# MyCar.net
KiCad netlist of a schematic drawn in Altium Designer
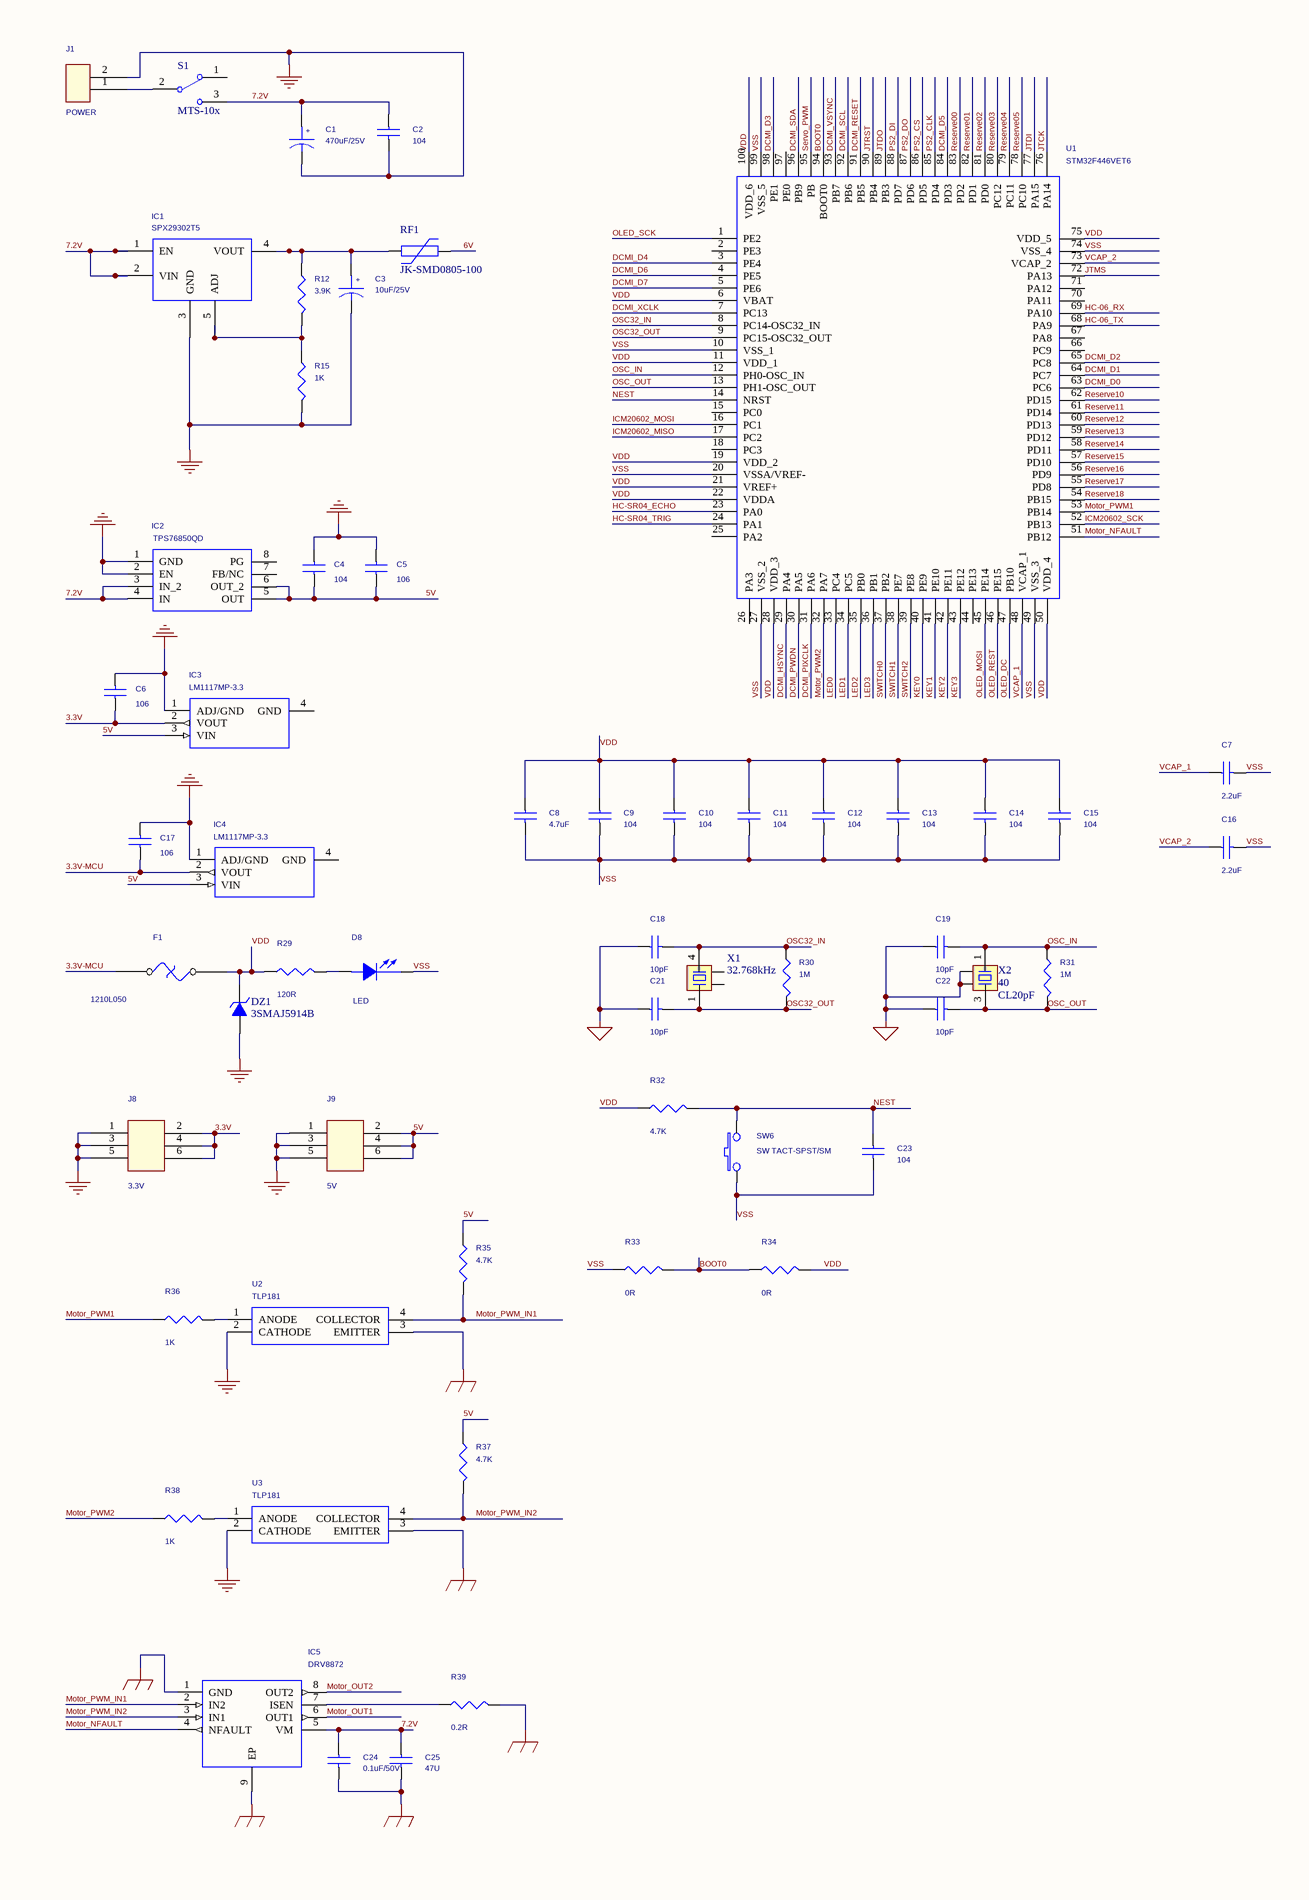
[diagram p0: MyCar.SchDoc, left]
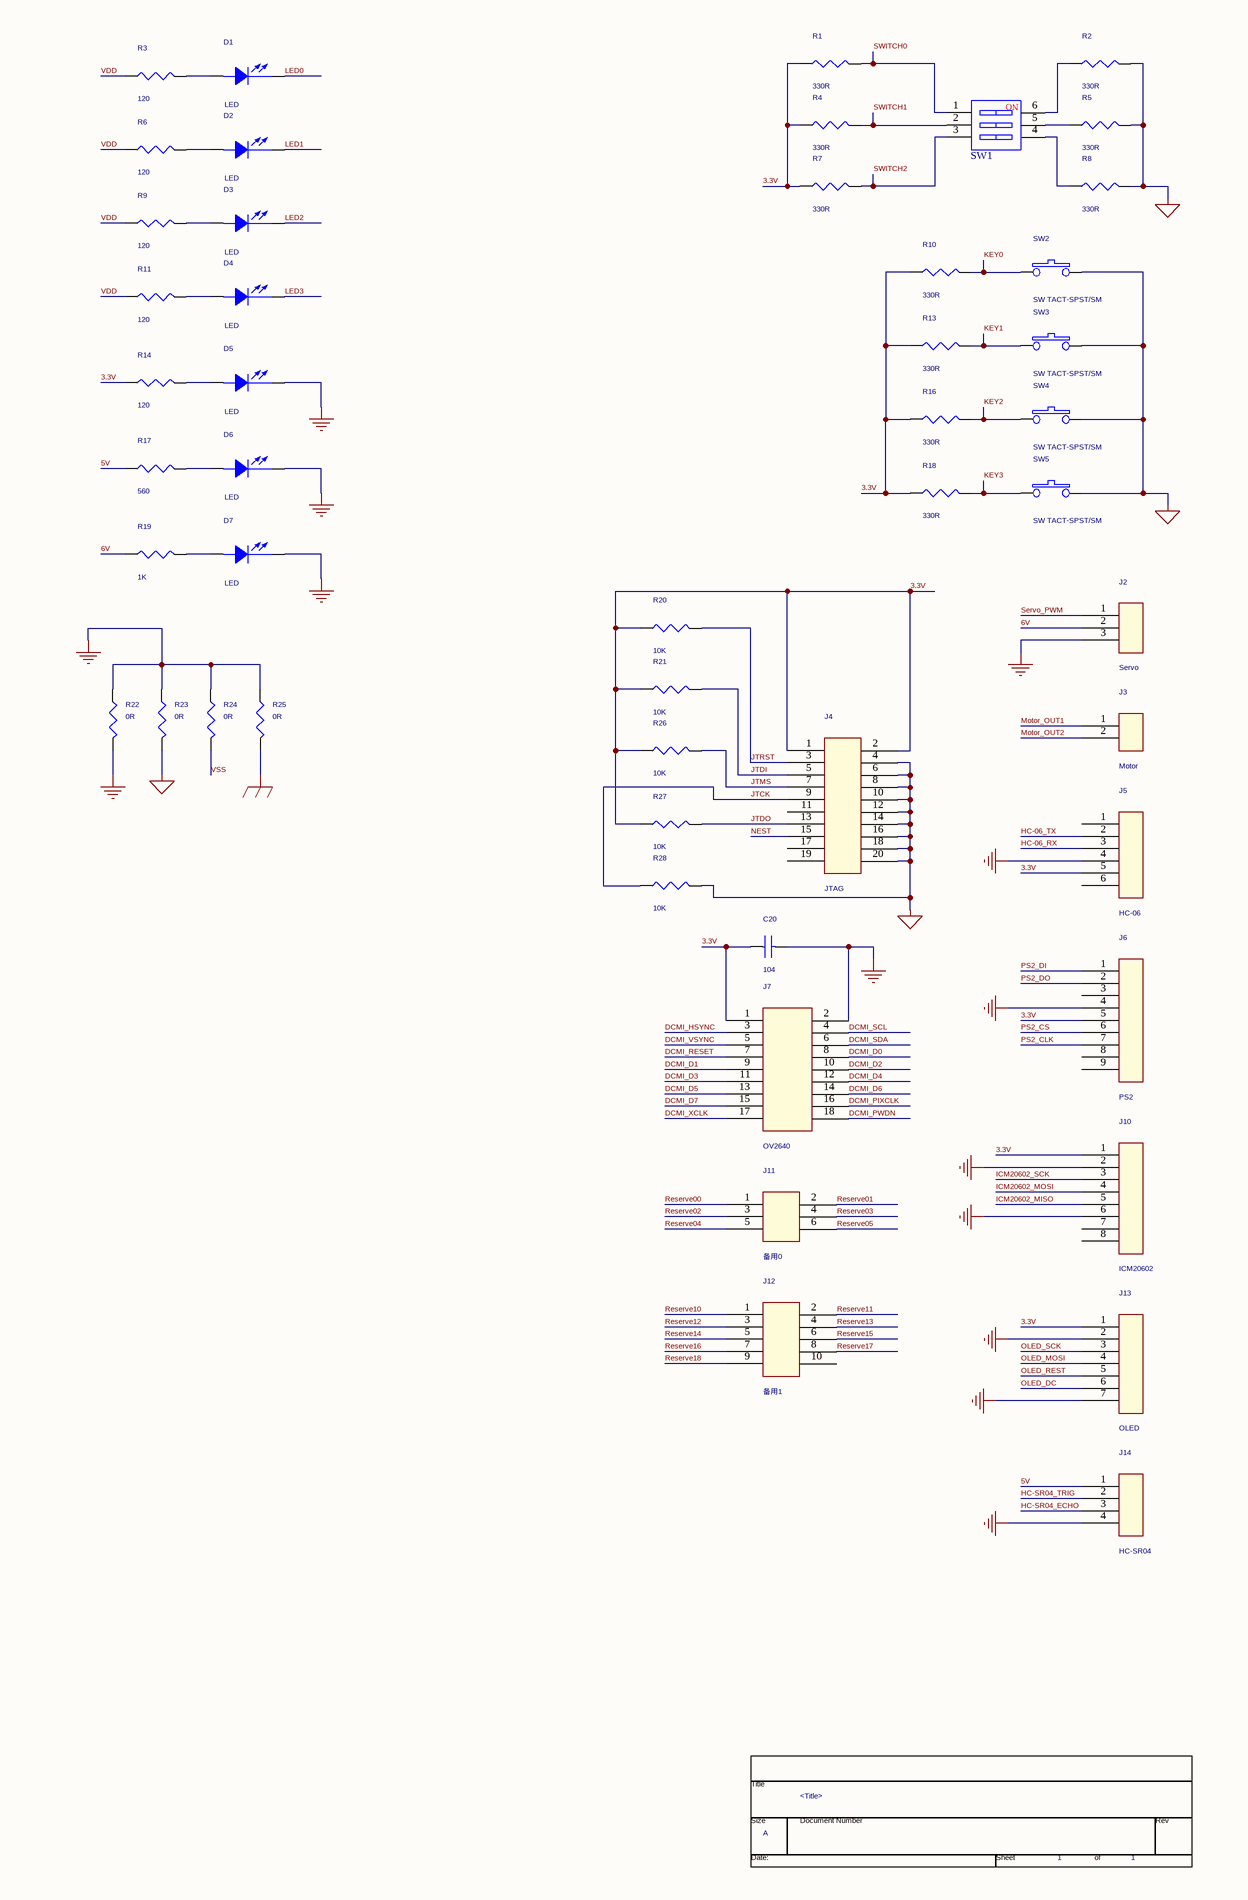
[diagram p1: MyCar.SchDoc, right]

(export (version "E")
  (design (tool "Eeschema 10.0.6"))
  (components
    (comp (ref "*")
      (value "TitleBlock0")
      (fields
        (field (name "TITLE") "<Title>")
        (field (name "PAGE SIZE") "A")
        (field (name "PAGE NUMBER") "1")
        (field (name "PAGE COUNT") "1")
      )
      (libsource (lib "*") (part "TitleBlock0"))
    )
    (comp (ref "C1") (value "470uF/25V") (footprint "CAP 3.5*8*11.5") (libsource (lib "*") (part "CAP POL")))
    (comp (ref "C2") (value "104") (footprint "C 0805_M") (libsource (lib "*") (part "CAP NP")))
    (comp (ref "C3") (value "10uF/25V") (footprint "CAP 2.0*5*7") (libsource (lib "*") (part "CAP POL")))
    (comp (ref "C4") (value "104") (footprint "C 0805_M") (libsource (lib "*") (part "CAP NP")))
    (comp (ref "C5") (value "106") (footprint "C 0805_M") (libsource (lib "*") (part "CAP NP")))
    (comp (ref "C6") (value "106") (footprint "C 0805_M") (libsource (lib "*") (part "CAP NP")))
    (comp (ref "C7") (value "2.2uF") (footprint "CD A(3216)") (libsource (lib "*") (part "CAP NP")))
    (comp (ref "C8") (value "4.7uF") (footprint "C 1210_M") (libsource (lib "*") (part "CAP NP")))
    (comp (ref "C9") (value "104") (footprint "C 0805_M") (libsource (lib "*") (part "CAP NP")))
    (comp (ref "C10") (value "104") (footprint "C 0805_M") (libsource (lib "*") (part "CAP NP")))
    (comp (ref "C11") (value "104") (footprint "C 0805_M") (libsource (lib "*") (part "CAP NP")))
    (comp (ref "C12") (value "104") (footprint "C 0805_M") (libsource (lib "*") (part "CAP NP")))
    (comp (ref "C13") (value "104") (footprint "C 0805_M") (libsource (lib "*") (part "CAP NP")))
    (comp (ref "C14") (value "104") (footprint "C 0805_M") (libsource (lib "*") (part "CAP NP")))
    (comp (ref "C15") (value "104") (footprint "C 0805_M") (libsource (lib "*") (part "CAP NP")))
    (comp (ref "C16") (value "2.2uF") (footprint "CD A(3216)") (libsource (lib "*") (part "CAP NP")))
    (comp (ref "C17") (value "106") (footprint "C 0805_M") (libsource (lib "*") (part "CAP NP")))
    (comp (ref "C18") (value "10pF") (footprint "C 0805_M") (libsource (lib "*") (part "CAP NP")))
    (comp (ref "C19") (value "10pF") (footprint "C 0805_M") (libsource (lib "*") (part "CAP NP")))
    (comp (ref "C20") (value "104") (footprint "C 0805_M") (libsource (lib "*") (part "CAP NP")))
    (comp (ref "C21") (value "10pF") (footprint "C 0805_M") (libsource (lib "*") (part "CAP NP")))
    (comp (ref "C22") (value "10pF") (footprint "C 0805_M") (libsource (lib "*") (part "CAP NP")))
    (comp (ref "C23") (value "104") (footprint "C 0805_M") (libsource (lib "*") (part "CAP NP")))
    (comp (ref "C24") (value "0.1uF/50V") (footprint "C 0603_M") (libsource (lib "*") (part "CAP NP")))
    (comp (ref "C25") (value "47U") (footprint "CAP 2.5*5*11") (libsource (lib "*") (part "CAP NP")))
    (comp (ref "D1") (value "LED") (footprint "LED 0805R") (libsource (lib "*") (part "LED")))
    (comp (ref "D2") (value "LED") (footprint "LED 0805R") (libsource (lib "*") (part "LED")))
    (comp (ref "D3") (value "LED") (footprint "LED 0805R") (libsource (lib "*") (part "LED")))
    (comp (ref "D4") (value "LED") (footprint "LED 0805R") (libsource (lib "*") (part "LED")))
    (comp (ref "D5") (value "LED") (footprint "LED 0805R") (libsource (lib "*") (part "LED")))
    (comp (ref "D6") (value "LED") (footprint "LED 0805R") (libsource (lib "*") (part "LED")))
    (comp (ref "D7") (value "LED") (footprint "LED 0805R") (libsource (lib "*") (part "LED")))
    (comp (ref "D8") (value "LED") (footprint "LED 0805R") (libsource (lib "*") (part "LED")))
    (comp (ref "DZ1")
      (value "3SMAJ5914B")
      (footprint "SMA DO-214AC")
      (description "3.0瓦表面贴装硅稳压二极管")
      (fields (field (name "版权归属") "源创客"))
      (libsource (lib "8.1   - 二极管-整流桥") (part "1N4619"))
    )
    (comp (ref "F1") (value "1210L050") (footprint "0805") (libsource (lib "*") (part "FUSE THERMAL")))
    (comp (ref "IC1") (value "SPX29302T5") (footprint "TO-263-5") (libsource (lib "*") (part "SPX29302T5")))
    (comp (ref "IC2")
      (value "TPS76850QD")
      (footprint "SOIC-8")
      (description "ULTRALOW QUIESCENT CURRENT 250-mA  LOW DROPOUT VOLTAGE REGULATORS")
      (fields (field (name "MOUSER PART NUMBER") "595-TPS76850QD"))
      (libsource (lib "*") (part "TPS76850QD"))
    )
    (comp (ref "IC3")
      (value "LM1117MP-3.3")
      (footprint "SOT-223")
      (description "Space saving 800-mA low-dropout linear regulator with internal current limit")
      (fields (field (name "MOUSER PART NUMBER") "926-LM1117MP-3.3NOPB"))
      (libsource (lib "*") (part "LM1117MP-3.3"))
    )
    (comp (ref "IC4")
      (value "LM1117MP-3.3")
      (footprint "SOT-223")
      (description "Space saving 800-mA low-dropout linear regulator with internal current limit")
      (fields (field (name "MOUSER PART NUMBER") "926-LM1117MP-3.3NOPB"))
      (libsource (lib "*") (part "LM1117MP-3.3"))
    )
    (comp (ref "IC5")
      (value "DRV8872")
      (footprint "SOP-8")
      (description "3.6A Brushed DC Motor Driver With Fault Reporting (PWM Ctrl)")
      (fields
        (field (name "ARROW PART NUMBER") "DRV8872DDAR")
        (field (name "MOUSER PART NUMBER") "595-DRV8872DDAR")
      )
      (libsource (lib "*") (part "DRV8872"))
    )
    (comp (ref "J1") (value "POWER") (footprint "KF2EDGK5.08-LI-2P") (libsource (lib "*") (part "CON2")))
    (comp (ref "J2") (value "Servo") (footprint "HDR2.54-LI-3P") (libsource (lib "*") (part "CON3")))
    (comp (ref "J3") (value "Motor") (footprint "KF2EDGK5.08-LI-2P") (libsource (lib "") (part "CON2_1")))
    (comp (ref "J4") (value "JTAG") (footprint "DC-2.54-L-Z-20P") (libsource (lib "*") (part "CON20A")))
    (comp (ref "J5") (value "HC-06") (footprint "HDR2.54-LI-6P") (libsource (lib "*") (part "CON6")))
    (comp (ref "J6") (value "PS2") (footprint "PS2") (libsource (lib "*") (part "CON9")))
    (comp (ref "J7") (value "OV2640") (footprint "HDR2.54-LI-2x9P") (libsource (lib "*") (part "CON18A")))
    (comp (ref "J8") (value "3.3V") (footprint "HDR2.54-LI-2x3P") (libsource (lib "*") (part "CON6A")))
    (comp (ref "J9") (value "5V") (footprint "HDR2.54-LI-2x3P") (libsource (lib "*") (part "CON6A")))
    (comp (ref "J10") (value "ICM20602") (footprint "HDR2.54-LI-8P") (libsource (lib "*") (part "CON8")))
    (comp (ref "J11") (value "备用0") (footprint "HDR2.54-LI-2x3P") (libsource (lib "*") (part "CON6A")))
    (comp (ref "J12") (value "备用1") (footprint "HDR2.54-LI-2x5P") (libsource (lib "*") (part "CON10A")))
    (comp (ref "J13") (value "OLED") (footprint "HDR2.54-LI-7P") (libsource (lib "*") (part "CON7")))
    (comp (ref "J14") (value "HC-SR04") (footprint "HDR2.54-LI-4P") (libsource (lib "*") (part "CON4")))
    (comp (ref "R1") (value "330R") (footprint "R 0805_M") (libsource (lib "*") (part "R")))
    (comp (ref "R2") (value "330R") (footprint "R 0805_M") (libsource (lib "*") (part "R")))
    (comp (ref "R3") (value "120") (footprint "R 0805_M") (libsource (lib "*") (part "R")))
    (comp (ref "R4") (value "330R") (footprint "R 0805_M") (libsource (lib "*") (part "R")))
    (comp (ref "R5") (value "330R") (footprint "R 0805_M") (libsource (lib "*") (part "R")))
    (comp (ref "R6") (value "120") (footprint "R 0805_M") (libsource (lib "*") (part "R")))
    (comp (ref "R7") (value "330R") (footprint "R 0805_M") (libsource (lib "*") (part "R")))
    (comp (ref "R8") (value "330R") (footprint "R 0805_M") (libsource (lib "*") (part "R")))
    (comp (ref "R9") (value "120") (footprint "R 0805_M") (libsource (lib "*") (part "R")))
    (comp (ref "R10") (value "330R") (footprint "R 0805_M") (libsource (lib "*") (part "R")))
    (comp (ref "R11") (value "120") (footprint "R 0805_M") (libsource (lib "*") (part "R")))
    (comp (ref "R12") (value "3.9K") (footprint "R 0805_M") (libsource (lib "*") (part "R")))
    (comp (ref "R13") (value "330R") (footprint "R 0805_M") (libsource (lib "*") (part "R")))
    (comp (ref "R14") (value "120") (footprint "R 0805_M") (libsource (lib "*") (part "R")))
    (comp (ref "R15") (value "1K") (footprint "R 0805_M") (libsource (lib "*") (part "R")))
    (comp (ref "R16") (value "330R") (footprint "R 0805_M") (libsource (lib "*") (part "R")))
    (comp (ref "R17") (value "560") (footprint "R 0805_M") (libsource (lib "*") (part "R")))
    (comp (ref "R18") (value "330R") (footprint "R 0805_M") (libsource (lib "*") (part "R")))
    (comp (ref "R19") (value "1K") (footprint "R 0805_M") (libsource (lib "*") (part "R")))
    (comp (ref "R20") (value "10K") (footprint "R 0805_M") (libsource (lib "*") (part "R")))
    (comp (ref "R21") (value "10K") (footprint "R 0805_M") (libsource (lib "*") (part "R")))
    (comp (ref "R22") (value "0R") (footprint "R 0805_M") (libsource (lib "*") (part "R")))
    (comp (ref "R23") (value "0R") (footprint "R 0805_M") (libsource (lib "*") (part "R")))
    (comp (ref "R24") (value "0R") (footprint "R 0805_M") (libsource (lib "*") (part "R")))
    (comp (ref "R25") (value "0R") (footprint "R 0805_M") (libsource (lib "*") (part "R")))
    (comp (ref "R26") (value "10K") (footprint "R 0805_M") (libsource (lib "*") (part "R")))
    (comp (ref "R27") (value "10K") (footprint "R 0805_M") (libsource (lib "*") (part "R")))
    (comp (ref "R28") (value "10K") (footprint "R 0805_M") (libsource (lib "*") (part "R")))
    (comp (ref "R29") (value "120R") (footprint "R 0805_M") (libsource (lib "*") (part "R")))
    (comp (ref "R30") (value "1M") (footprint "R 0805_M") (libsource (lib "*") (part "R")))
    (comp (ref "R31") (value "1M") (footprint "R 0805_M") (libsource (lib "*") (part "R")))
    (comp (ref "R32") (value "4.7K") (footprint "R 0805_M") (libsource (lib "*") (part "R")))
    (comp (ref "R33") (value "0R") (footprint "R 0805_M") (libsource (lib "*") (part "R")))
    (comp (ref "R34") (value "0R") (footprint "R 0805_M") (libsource (lib "*") (part "R")))
    (comp (ref "R35") (value "4.7K") (footprint "R 0805_M") (libsource (lib "*") (part "R")))
    (comp (ref "R36") (value "1K") (footprint "R 0805_M") (libsource (lib "*") (part "R")))
    (comp (ref "R37") (value "4.7K") (footprint "R 0805_M") (libsource (lib "*") (part "R")))
    (comp (ref "R38") (value "1K") (footprint "R 0805_M") (libsource (lib "*") (part "R")))
    (comp (ref "R39") (value "0.2R") (footprint "R 1206_M") (libsource (lib "*") (part "R")))
    (comp (ref "RF1")
      (value "JK-SMD0805-100")
      (footprint "FU 0805")
      (description "PPTC自恢复保险丝")
      (fields (field (name "版权归属") "源创客"))
      (libsource (lib "10.1 - 保险丝-晶振") (part "PPTC"))
    )
    (comp (ref "S1")
      (value "MTS-10x")
      (footprint "MTS-10x")
      (description "MTS10x系列3脚扭子开关")
      (fields (field (name "版权归属") "源创客"))
      (libsource (lib "5.1   - 按键-开关") (part "MTS-10x"))
    )
    (comp (ref "SW1")
      (value "CSW-3P")
      (footprint "CSW DIP-3P")
      (description "3路编码开关")
      (fields (field (name "版权归属") "源创客"))
      (libsource (lib "按键-开关") (part "CSW-3P"))
    )
    (comp (ref "SW2")
      (value "SW TACT-SPST/SM")
      (footprint "TSW DIP-6*6*4.3")
      (libsource (lib "*") (part "SW TACT-SPST/SM"))
    )
    (comp (ref "SW3")
      (value "SW TACT-SPST/SM")
      (footprint "TSW DIP-6*6*4.3")
      (libsource (lib "*") (part "SW TACT-SPST/SM"))
    )
    (comp (ref "SW4")
      (value "SW TACT-SPST/SM")
      (footprint "TSW DIP-6*6*4.3")
      (libsource (lib "*") (part "SW TACT-SPST/SM"))
    )
    (comp (ref "SW5")
      (value "SW TACT-SPST/SM")
      (footprint "TSW DIP-6*6*4.3")
      (libsource (lib "*") (part "SW TACT-SPST/SM"))
    )
    (comp (ref "SW6")
      (value "SW TACT-SPST/SM")
      (footprint "TSW DIP-6*6*4.3")
      (libsource (lib "*") (part "SW TACT-SPST/SM"))
    )
    (comp (ref "U1")
      (value "STM32F446VET6")
      (footprint "LQFP100 14x14_N")
      (description "STMICROELECTRONICS - STM32F446VET6 - MCU, 32BIT, CORTEX-M4, 180MHZ, LQFP-100")
      (fields (field (name "MOUSER PART NUMBER") "511-STM32F446VET6"))
      (libsource (lib "*") (part "STM32F446VET6"))
    )
    (comp (ref "U2")
      (value "TLP181")
      (footprint "SOP4_M")
      (description "Transistor Output Optocouplers 80V Photocoupler 3750 Vrms 100 to 600")
      (fields
        (field (name "MOUSER PART NUMBER") "757-TLP181GBTPLF")
        (field (name "MANUFACTURER_PART_NUMBER") "TLP181(GB-TPL,F)")
      )
      (libsource (lib "*") (part "TLP181"))
    )
    (comp (ref "U3")
      (value "TLP181")
      (footprint "SOP4_M")
      (description "Transistor Output Optocouplers 80V Photocoupler 3750 Vrms 100 to 600")
      (fields
        (field (name "MOUSER PART NUMBER") "757-TLP181GBTPLF")
        (field (name "MANUFACTURER_PART_NUMBER") "TLP181(GB-TPL,F)")
      )
      (libsource (lib "*") (part "TLP181"))
    )
    (comp (ref "X1")
      (value "32.768kHz")
      (footprint "OSC MC-146")
      (description "MC系列4脚晶振")
      (fields (field (name "版权归属") "源创客"))
      (libsource (lib "10.1 - 保险丝-晶振") (part "XTAL-MC-4P"))
    )
    (comp (ref "X2")
      (value "40")
      (footprint "OSC 3225-4P")
      (description "4脚无源晶振")
      (fields (field (name "负载电容") "CL20pF") (field (name "版权归属") "源创客"))
      (libsource (lib "10.1 - 保险丝-晶振") (part "XTAL-4P"))
    )
  )
  (nets
    (net (code "1") (name "/3.3V") (class "Default")
      (node (ref "C20") (pin "1") (pinfunction "1_1") (pintype "passive"))
      (node (ref "C6") (pin "1") (pinfunction "1_1") (pintype "passive"))
      (node (ref "IC3") (pin "2") (pinfunction "VOUT_2") (pintype "output"))
      (node (ref "J10") (pin "1") (pinfunction "1_1") (pintype "passive"))
      (node (ref "J13") (pin "1") (pinfunction "1_1") (pintype "passive"))
      (node (ref "J4") (pin "1") (pinfunction "1_1") (pintype "passive"))
      (node (ref "J4") (pin "2") (pinfunction "2_2") (pintype "passive"))
      (node (ref "J5") (pin "5") (pinfunction "5_5") (pintype "passive"))
      (node (ref "J6") (pin "5") (pinfunction "5_5") (pintype "passive"))
      (node (ref "J7") (pin "1") (pinfunction "1_1") (pintype "passive"))
      (node (ref "J8") (pin "2") (pinfunction "2_2") (pintype "passive"))
      (node (ref "J8") (pin "4") (pinfunction "4_4") (pintype "passive"))
      (node (ref "J8") (pin "6") (pinfunction "6_6") (pintype "passive"))
      (node (ref "R1") (pin "1") (pinfunction "1_1") (pintype "passive"))
      (node (ref "R10") (pin "1") (pinfunction "1_1") (pintype "passive"))
      (node (ref "R13") (pin "1") (pinfunction "1_1") (pintype "passive"))
      (node (ref "R14") (pin "1") (pinfunction "1_1") (pintype "passive"))
      (node (ref "R16") (pin "1") (pinfunction "1_1") (pintype "passive"))
      (node (ref "R18") (pin "1") (pinfunction "1_1") (pintype "passive"))
      (node (ref "R20") (pin "1") (pinfunction "1_1") (pintype "passive"))
      (node (ref "R21") (pin "1") (pinfunction "1_1") (pintype "passive"))
      (node (ref "R26") (pin "1") (pinfunction "1_1") (pintype "passive"))
      (node (ref "R27") (pin "1") (pinfunction "1_1") (pintype "passive"))
      (node (ref "R4") (pin "1") (pinfunction "1_1") (pintype "passive"))
      (node (ref "R7") (pin "1") (pinfunction "1_1") (pintype "passive"))
    )
    (net (code "2") (name "/3.3V-MCU") (class "Default")
      (node (ref "C17") (pin "1") (pinfunction "1_1") (pintype "passive"))
      (node (ref "F1") (pin "1") (pinfunction "1_1") (pintype "passive"))
      (node (ref "IC4") (pin "2") (pinfunction "VOUT_2") (pintype "output"))
    )
    (net (code "3") (name "/5V") (class "Default")
      (node (ref "C4") (pin "1") (pinfunction "1_1") (pintype "passive"))
      (node (ref "C5") (pin "1") (pinfunction "1_1") (pintype "passive"))
      (node (ref "IC2") (pin "5") (pinfunction "OUT_5") (pintype "passive"))
      (node (ref "IC2") (pin "6") (pinfunction "OUT_2_6") (pintype "passive"))
      (node (ref "IC3") (pin "3") (pinfunction "VIN_3") (pintype "input"))
      (node (ref "IC4") (pin "3") (pinfunction "VIN_3") (pintype "input"))
      (node (ref "J14") (pin "1") (pinfunction "1_1") (pintype "passive"))
      (node (ref "J9") (pin "2") (pinfunction "2_2") (pintype "passive"))
      (node (ref "J9") (pin "4") (pinfunction "4_4") (pintype "passive"))
      (node (ref "J9") (pin "6") (pinfunction "6_6") (pintype "passive"))
      (node (ref "R17") (pin "1") (pinfunction "1_1") (pintype "passive"))
      (node (ref "R35") (pin "1") (pinfunction "1_1") (pintype "passive"))
      (node (ref "R37") (pin "1") (pinfunction "1_1") (pintype "passive"))
    )
    (net (code "4") (name "/6V") (class "Default")
      (node (ref "J2") (pin "2") (pinfunction "2_2") (pintype "passive"))
      (node (ref "R19") (pin "1") (pinfunction "1_1") (pintype "passive"))
      (node (ref "RF1") (pin "2") (pinfunction "2_2") (pintype "passive"))
    )
    (net (code "5") (name "/7.2V") (class "Default")
      (node (ref "C1") (pin "1") (pinfunction "1_1") (pintype "passive"))
      (node (ref "C2") (pin "1") (pinfunction "1_1") (pintype "passive"))
      (node (ref "C24") (pin "1") (pinfunction "1_1") (pintype "passive"))
      (node (ref "C25") (pin "1") (pinfunction "1_1") (pintype "passive"))
      (node (ref "IC1") (pin "1") (pinfunction "EN_1") (pintype "power_in"))
      (node (ref "IC1") (pin "2") (pinfunction "VIN_2") (pintype "power_in"))
      (node (ref "IC2") (pin "3") (pinfunction "IN_2_3") (pintype "passive"))
      (node (ref "IC2") (pin "4") (pinfunction "IN_4") (pintype "passive"))
      (node (ref "IC5") (pin "5") (pinfunction "VM_5") (pintype "power_in"))
      (node (ref "S1") (pin "3") (pinfunction "3_3") (pintype "passive"))
    )
    (net (code "6") (name "/BOOT0") (class "Default")
      (node (ref "R33") (pin "2") (pinfunction "2_2") (pintype "passive"))
      (node (ref "R34") (pin "1") (pinfunction "1_1") (pintype "passive"))
      (node (ref "U1") (pin "94") (pinfunction "BOOT0_94") (pintype "passive"))
    )
    (net (code "7") (name "/DCMI_D0") (class "Default")
      (node (ref "J7") (pin "8") (pinfunction "8_8") (pintype "passive"))
      (node (ref "U1") (pin "63") (pinfunction "PC6_63") (pintype "passive"))
    )
    (net (code "8") (name "/DCMI_D1") (class "Default")
      (node (ref "J7") (pin "9") (pinfunction "9_9") (pintype "passive"))
      (node (ref "U1") (pin "64") (pinfunction "PC7_64") (pintype "passive"))
    )
    (net (code "9") (name "/DCMI_D2") (class "Default")
      (node (ref "J7") (pin "10") (pinfunction "10_10") (pintype "passive"))
      (node (ref "U1") (pin "65") (pinfunction "PC8_65") (pintype "passive"))
    )
    (net (code "10") (name "/DCMI_D3") (class "Default")
      (node (ref "J7") (pin "11") (pinfunction "11_11") (pintype "passive"))
      (node (ref "U1") (pin "98") (pinfunction "PE1_98") (pintype "passive"))
    )
    (net (code "11") (name "/DCMI_D4") (class "Default")
      (node (ref "J7") (pin "12") (pinfunction "12_12") (pintype "passive"))
      (node (ref "U1") (pin "3") (pinfunction "PE4_3") (pintype "passive"))
    )
    (net (code "12") (name "/DCMI_D5") (class "Default")
      (node (ref "J7") (pin "13") (pinfunction "13_13") (pintype "passive"))
      (node (ref "U1") (pin "84") (pinfunction "PD3_84") (pintype "passive"))
    )
    (net (code "13") (name "/DCMI_D6") (class "Default")
      (node (ref "J7") (pin "14") (pinfunction "14_14") (pintype "passive"))
      (node (ref "U1") (pin "4") (pinfunction "PE5_4") (pintype "passive"))
    )
    (net (code "14") (name "/DCMI_D7") (class "Default")
      (node (ref "J7") (pin "15") (pinfunction "15_15") (pintype "passive"))
      (node (ref "U1") (pin "5") (pinfunction "PE6_5") (pintype "passive"))
    )
    (net (code "15") (name "/DCMI_HSYNC") (class "Default")
      (node (ref "J7") (pin "3") (pinfunction "3_3") (pintype "passive"))
      (node (ref "U1") (pin "29") (pinfunction "PA4_29") (pintype "passive"))
    )
    (net (code "16") (name "/DCMI_PIXCLK") (class "Default")
      (node (ref "J7") (pin "16") (pinfunction "16_16") (pintype "passive"))
      (node (ref "U1") (pin "31") (pinfunction "PA6_31") (pintype "passive"))
    )
    (net (code "17") (name "/DCMI_PWDN") (class "Default")
      (node (ref "J7") (pin "18") (pinfunction "18_18") (pintype "passive"))
      (node (ref "U1") (pin "30") (pinfunction "PA5_30") (pintype "passive"))
    )
    (net (code "18") (name "/DCMI_RESET") (class "Default")
      (node (ref "J7") (pin "7") (pinfunction "7_7") (pintype "passive"))
      (node (ref "U1") (pin "91") (pinfunction "PB5_91") (pintype "passive"))
    )
    (net (code "19") (name "/DCMI_SCL") (class "Default")
      (node (ref "J7") (pin "4") (pinfunction "4_4") (pintype "passive"))
      (node (ref "U1") (pin "92") (pinfunction "PB6_92") (pintype "passive"))
    )
    (net (code "20") (name "/DCMI_SDA") (class "Default")
      (node (ref "J7") (pin "6") (pinfunction "6_6") (pintype "passive"))
      (node (ref "U1") (pin "96") (pinfunction "PB9_96") (pintype "passive"))
    )
    (net (code "21") (name "/DCMI_VSYNC") (class "Default")
      (node (ref "J7") (pin "5") (pinfunction "5_5") (pintype "passive"))
      (node (ref "U1") (pin "93") (pinfunction "PB7_93") (pintype "passive"))
    )
    (net (code "22") (name "/DCMI_XCLK") (class "Default")
      (node (ref "J7") (pin "17") (pinfunction "17_17") (pintype "passive"))
      (node (ref "U1") (pin "7") (pinfunction "PC13_7") (pintype "passive"))
    )
    (net (code "23") (name "/HC-06_RX") (class "Default")
      (node (ref "J5") (pin "3") (pinfunction "3_3") (pintype "passive"))
      (node (ref "U1") (pin "69") (pinfunction "PA10_69") (pintype "passive"))
    )
    (net (code "24") (name "/HC-06_TX") (class "Default")
      (node (ref "J5") (pin "2") (pinfunction "2_2") (pintype "passive"))
      (node (ref "U1") (pin "68") (pinfunction "PA9_68") (pintype "passive"))
    )
    (net (code "25") (name "/HC-SR04_ECHO") (class "Default")
      (node (ref "J14") (pin "3") (pinfunction "3_3") (pintype "passive"))
      (node (ref "U1") (pin "23") (pinfunction "PA0_23") (pintype "passive"))
    )
    (net (code "26") (name "/HC-SR04_TRIG") (class "Default")
      (node (ref "J14") (pin "2") (pinfunction "2_2") (pintype "passive"))
      (node (ref "U1") (pin "24") (pinfunction "PA1_24") (pintype "passive"))
    )
    (net (code "27") (name "/ICM20602_MISO") (class "Default")
      (node (ref "J10") (pin "5") (pinfunction "5_5") (pintype "passive"))
      (node (ref "U1") (pin "17") (pinfunction "PC2_17") (pintype "passive"))
    )
    (net (code "28") (name "/ICM20602_MOSI") (class "Default")
      (node (ref "J10") (pin "4") (pinfunction "4_4") (pintype "passive"))
      (node (ref "U1") (pin "16") (pinfunction "PC1_16") (pintype "passive"))
    )
    (net (code "29") (name "/ICM20602_SCK") (class "Default")
      (node (ref "J10") (pin "3") (pinfunction "3_3") (pintype "passive"))
      (node (ref "U1") (pin "52") (pinfunction "PB13_52") (pintype "passive"))
    )
    (net (code "30") (name "/JTCK") (class "Default")
      (node (ref "J4") (pin "9") (pinfunction "9_9") (pintype "passive"))
      (node (ref "R28") (pin "1") (pinfunction "1_1") (pintype "passive"))
      (node (ref "U1") (pin "76") (pinfunction "PA14_76") (pintype "passive"))
    )
    (net (code "31") (name "/JTDI") (class "Default")
      (node (ref "J4") (pin "5") (pinfunction "5_5") (pintype "passive"))
      (node (ref "R21") (pin "2") (pinfunction "2_2") (pintype "passive"))
      (node (ref "U1") (pin "77") (pinfunction "PA15_77") (pintype "passive"))
    )
    (net (code "32") (name "/JTDO") (class "Default")
      (node (ref "J4") (pin "13") (pinfunction "13_13") (pintype "passive"))
      (node (ref "R27") (pin "2") (pinfunction "2_2") (pintype "passive"))
      (node (ref "U1") (pin "89") (pinfunction "PB3_89") (pintype "passive"))
    )
    (net (code "33") (name "/JTMS") (class "Default")
      (node (ref "J4") (pin "7") (pinfunction "7_7") (pintype "passive"))
      (node (ref "R26") (pin "2") (pinfunction "2_2") (pintype "passive"))
      (node (ref "U1") (pin "72") (pinfunction "PA13_72") (pintype "passive"))
    )
    (net (code "34") (name "/JTRST") (class "Default")
      (node (ref "J4") (pin "3") (pinfunction "3_3") (pintype "passive"))
      (node (ref "R20") (pin "2") (pinfunction "2_2") (pintype "passive"))
      (node (ref "U1") (pin "90") (pinfunction "PB4_90") (pintype "passive"))
    )
    (net (code "35") (name "/KEY0") (class "Default")
      (node (ref "R10") (pin "2") (pinfunction "2_2") (pintype "passive"))
      (node (ref "SW2") (pin "1") (pinfunction "1_1") (pintype "passive"))
      (node (ref "U1") (pin "40") (pinfunction "PE9_40") (pintype "passive"))
    )
    (net (code "36") (name "/KEY1") (class "Default")
      (node (ref "R13") (pin "2") (pinfunction "2_2") (pintype "passive"))
      (node (ref "SW3") (pin "1") (pinfunction "1_1") (pintype "passive"))
      (node (ref "U1") (pin "41") (pinfunction "PE10_41") (pintype "passive"))
    )
    (net (code "37") (name "/KEY2") (class "Default")
      (node (ref "R16") (pin "2") (pinfunction "2_2") (pintype "passive"))
      (node (ref "SW4") (pin "1") (pinfunction "1_1") (pintype "passive"))
      (node (ref "U1") (pin "42") (pinfunction "PE11_42") (pintype "passive"))
    )
    (net (code "38") (name "/KEY3") (class "Default")
      (node (ref "R18") (pin "2") (pinfunction "2_2") (pintype "passive"))
      (node (ref "SW5") (pin "1") (pinfunction "1_1") (pintype "passive"))
      (node (ref "U1") (pin "43") (pinfunction "PE12_43") (pintype "passive"))
    )
    (net (code "39") (name "/LED0") (class "Default")
      (node (ref "D1") (pin "1") (pinfunction "CATHODE_1") (pintype "passive"))
      (node (ref "U1") (pin "33") (pinfunction "PC4_33") (pintype "passive"))
    )
    (net (code "40") (name "/LED1") (class "Default")
      (node (ref "D2") (pin "1") (pinfunction "CATHODE_1") (pintype "passive"))
      (node (ref "U1") (pin "34") (pinfunction "PC5_34") (pintype "passive"))
    )
    (net (code "41") (name "/LED2") (class "Default")
      (node (ref "D3") (pin "1") (pinfunction "CATHODE_1") (pintype "passive"))
      (node (ref "U1") (pin "35") (pinfunction "PB0_35") (pintype "passive"))
    )
    (net (code "42") (name "/LED3") (class "Default")
      (node (ref "D4") (pin "1") (pinfunction "CATHODE_1") (pintype "passive"))
      (node (ref "U1") (pin "36") (pinfunction "PB1_36") (pintype "passive"))
    )
    (net (code "43") (name "/Motor_NFAULT") (class "Default")
      (node (ref "IC5") (pin "4") (pinfunction "NFAULT_4") (pintype "output"))
      (node (ref "U1") (pin "51") (pinfunction "PB12_51") (pintype "passive"))
    )
    (net (code "44") (name "/Motor_OUT1") (class "Default")
      (node (ref "IC5") (pin "6") (pinfunction "OUT1_6") (pintype "output"))
      (node (ref "J3") (pin "1") (pinfunction "1_1") (pintype "passive"))
    )
    (net (code "45") (name "/Motor_OUT2") (class "Default")
      (node (ref "IC5") (pin "8") (pinfunction "OUT2_8") (pintype "output"))
      (node (ref "J3") (pin "2") (pinfunction "2_2") (pintype "passive"))
    )
    (net (code "46") (name "/Motor_PWM1") (class "Default")
      (node (ref "R36") (pin "1") (pinfunction "1_1") (pintype "passive"))
      (node (ref "U1") (pin "53") (pinfunction "PB14_53") (pintype "passive"))
    )
    (net (code "47") (name "/Motor_PWM2") (class "Default")
      (node (ref "R38") (pin "1") (pinfunction "1_1") (pintype "passive"))
      (node (ref "U1") (pin "32") (pinfunction "PA7_32") (pintype "passive"))
    )
    (net (code "48") (name "/Motor_PWM_IN1") (class "Default")
      (node (ref "IC5") (pin "2") (pinfunction "IN2_2") (pintype "input"))
      (node (ref "R35") (pin "2") (pinfunction "2_2") (pintype "passive"))
      (node (ref "U2") (pin "4") (pinfunction "COLLECTOR_4") (pintype "passive"))
    )
    (net (code "49") (name "/Motor_PWM_IN2") (class "Default")
      (node (ref "IC5") (pin "3") (pinfunction "IN1_3") (pintype "input"))
      (node (ref "R37") (pin "2") (pinfunction "2_2") (pintype "passive"))
      (node (ref "U3") (pin "4") (pinfunction "COLLECTOR_4") (pintype "passive"))
    )
    (net (code "50") (name "/NEST") (class "Default")
      (node (ref "C23") (pin "1") (pinfunction "1_1") (pintype "passive"))
      (node (ref "J4") (pin "15") (pinfunction "15_15") (pintype "passive"))
      (node (ref "R32") (pin "2") (pinfunction "2_2") (pintype "passive"))
      (node (ref "SW6") (pin "2") (pinfunction "2_2") (pintype "passive"))
      (node (ref "U1") (pin "14") (pinfunction "NRST_14") (pintype "passive"))
    )
    (net (code "51") (name "/OLED_DC") (class "Default")
      (node (ref "J13") (pin "6") (pinfunction "6_6") (pintype "passive"))
      (node (ref "U1") (pin "47") (pinfunction "PB10_47") (pintype "passive"))
    )
    (net (code "52") (name "/OLED_MOSI") (class "Default")
      (node (ref "J13") (pin "4") (pinfunction "4_4") (pintype "passive"))
      (node (ref "U1") (pin "45") (pinfunction "PE14_45") (pintype "passive"))
    )
    (net (code "53") (name "/OLED_REST") (class "Default")
      (node (ref "J13") (pin "5") (pinfunction "5_5") (pintype "passive"))
      (node (ref "U1") (pin "46") (pinfunction "PE15_46") (pintype "passive"))
    )
    (net (code "54") (name "/OLED_SCK") (class "Default")
      (node (ref "J13") (pin "3") (pinfunction "3_3") (pintype "passive"))
      (node (ref "U1") (pin "1") (pinfunction "PE2_1") (pintype "passive"))
    )
    (net (code "55") (name "/OSC32_IN") (class "Default")
      (node (ref "C18") (pin "2") (pinfunction "2_2") (pintype "passive"))
      (node (ref "R30") (pin "1") (pinfunction "1_1") (pintype "passive"))
      (node (ref "U1") (pin "8") (pinfunction "PC14-OSC32_IN_8") (pintype "passive"))
      (node (ref "X1") (pin "4") (pinfunction "4_4") (pintype "passive"))
    )
    (net (code "56") (name "/OSC32_OUT") (class "Default")
      (node (ref "C21") (pin "2") (pinfunction "2_2") (pintype "passive"))
      (node (ref "R30") (pin "2") (pinfunction "2_2") (pintype "passive"))
      (node (ref "U1") (pin "9") (pinfunction "PC15-OSC32_OUT_9") (pintype "passive"))
      (node (ref "X1") (pin "1") (pinfunction "1_1") (pintype "passive"))
    )
    (net (code "57") (name "/OSC_IN") (class "Default")
      (node (ref "C19") (pin "2") (pinfunction "2_2") (pintype "passive"))
      (node (ref "R31") (pin "1") (pinfunction "1_1") (pintype "passive"))
      (node (ref "U1") (pin "12") (pinfunction "PH0-OSC_IN_12") (pintype "passive"))
      (node (ref "X2") (pin "1") (pinfunction "1_1") (pintype "passive"))
    )
    (net (code "58") (name "/OSC_OUT") (class "Default")
      (node (ref "C22") (pin "2") (pinfunction "2_2") (pintype "passive"))
      (node (ref "R31") (pin "2") (pinfunction "2_2") (pintype "passive"))
      (node (ref "U1") (pin "13") (pinfunction "PH1-OSC_OUT_13") (pintype "passive"))
      (node (ref "X2") (pin "3") (pinfunction "3_3") (pintype "passive"))
    )
    (net (code "59") (name "/PS2_CLK") (class "Default")
      (node (ref "J6") (pin "7") (pinfunction "7_7") (pintype "passive"))
      (node (ref "U1") (pin "85") (pinfunction "PD4_85") (pintype "passive"))
    )
    (net (code "60") (name "/PS2_CS") (class "Default")
      (node (ref "J6") (pin "6") (pinfunction "6_6") (pintype "passive"))
      (node (ref "U1") (pin "86") (pinfunction "PD5_86") (pintype "passive"))
    )
    (net (code "61") (name "/PS2_DI") (class "Default")
      (node (ref "J6") (pin "1") (pinfunction "1_1") (pintype "passive"))
      (node (ref "U1") (pin "88") (pinfunction "PD7_88") (pintype "passive"))
    )
    (net (code "62") (name "/PS2_DO") (class "Default")
      (node (ref "J6") (pin "2") (pinfunction "2_2") (pintype "passive"))
      (node (ref "U1") (pin "87") (pinfunction "PD6_87") (pintype "passive"))
    )
    (net (code "63") (name "/Reserve00") (class "Default")
      (node (ref "J11") (pin "1") (pinfunction "1_1") (pintype "passive"))
      (node (ref "U1") (pin "83") (pinfunction "PD2_83") (pintype "passive"))
    )
    (net (code "64") (name "/Reserve01") (class "Default")
      (node (ref "J11") (pin "2") (pinfunction "2_2") (pintype "passive"))
      (node (ref "U1") (pin "82") (pinfunction "PD1_82") (pintype "passive"))
    )
    (net (code "65") (name "/Reserve02") (class "Default")
      (node (ref "J11") (pin "3") (pinfunction "3_3") (pintype "passive"))
      (node (ref "U1") (pin "81") (pinfunction "PD0_81") (pintype "passive"))
    )
    (net (code "66") (name "/Reserve03") (class "Default")
      (node (ref "J11") (pin "4") (pinfunction "4_4") (pintype "passive"))
      (node (ref "U1") (pin "80") (pinfunction "PC12_80") (pintype "passive"))
    )
    (net (code "67") (name "/Reserve04") (class "Default")
      (node (ref "J11") (pin "5") (pinfunction "5_5") (pintype "passive"))
      (node (ref "U1") (pin "79") (pinfunction "PC11_79") (pintype "passive"))
    )
    (net (code "68") (name "/Reserve05") (class "Default")
      (node (ref "J11") (pin "6") (pinfunction "6_6") (pintype "passive"))
      (node (ref "U1") (pin "78") (pinfunction "PC10_78") (pintype "passive"))
    )
    (net (code "69") (name "/Reserve10") (class "Default")
      (node (ref "J12") (pin "1") (pinfunction "1_1") (pintype "passive"))
      (node (ref "U1") (pin "62") (pinfunction "PD15_62") (pintype "passive"))
    )
    (net (code "70") (name "/Reserve11") (class "Default")
      (node (ref "J12") (pin "2") (pinfunction "2_2") (pintype "passive"))
      (node (ref "U1") (pin "61") (pinfunction "PD14_61") (pintype "passive"))
    )
    (net (code "71") (name "/Reserve12") (class "Default")
      (node (ref "J12") (pin "3") (pinfunction "3_3") (pintype "passive"))
      (node (ref "U1") (pin "60") (pinfunction "PD13_60") (pintype "passive"))
    )
    (net (code "72") (name "/Reserve13") (class "Default")
      (node (ref "J12") (pin "4") (pinfunction "4_4") (pintype "passive"))
      (node (ref "U1") (pin "59") (pinfunction "PD12_59") (pintype "passive"))
    )
    (net (code "73") (name "/Reserve14") (class "Default")
      (node (ref "J12") (pin "5") (pinfunction "5_5") (pintype "passive"))
      (node (ref "U1") (pin "58") (pinfunction "PD11_58") (pintype "passive"))
    )
    (net (code "74") (name "/Reserve15") (class "Default")
      (node (ref "J12") (pin "6") (pinfunction "6_6") (pintype "passive"))
      (node (ref "U1") (pin "57") (pinfunction "PD10_57") (pintype "passive"))
    )
    (net (code "75") (name "/Reserve16") (class "Default")
      (node (ref "J12") (pin "7") (pinfunction "7_7") (pintype "passive"))
      (node (ref "U1") (pin "56") (pinfunction "PD9_56") (pintype "passive"))
    )
    (net (code "76") (name "/Reserve17") (class "Default")
      (node (ref "J12") (pin "8") (pinfunction "8_8") (pintype "passive"))
      (node (ref "U1") (pin "55") (pinfunction "PD8_55") (pintype "passive"))
    )
    (net (code "77") (name "/Reserve18") (class "Default")
      (node (ref "J12") (pin "9") (pinfunction "9_9") (pintype "passive"))
      (node (ref "U1") (pin "54") (pinfunction "PB15_54") (pintype "passive"))
    )
    (net (code "78") (name "/SWITCH0") (class "Default")
      (node (ref "R1") (pin "2") (pinfunction "2_2") (pintype "passive"))
      (node (ref "SW1") (pin "1") (pinfunction "1_1") (pintype "passive"))
      (node (ref "U1") (pin "37") (pinfunction "PB2_37") (pintype "passive"))
    )
    (net (code "79") (name "/SWITCH1") (class "Default")
      (node (ref "R4") (pin "2") (pinfunction "2_2") (pintype "passive"))
      (node (ref "SW1") (pin "2") (pinfunction "2_2") (pintype "passive"))
      (node (ref "U1") (pin "38") (pinfunction "PE7_38") (pintype "passive"))
    )
    (net (code "80") (name "/SWITCH2") (class "Default")
      (node (ref "R7") (pin "2") (pinfunction "2_2") (pintype "passive"))
      (node (ref "SW1") (pin "3") (pinfunction "3_3") (pintype "passive"))
      (node (ref "U1") (pin "39") (pinfunction "PE8_39") (pintype "passive"))
    )
    (net (code "81") (name "/Servo_PWM") (class "Default")
      (node (ref "J2") (pin "1") (pinfunction "1_1") (pintype "passive"))
      (node (ref "U1") (pin "95") (pinfunction "PB_95") (pintype "passive"))
    )
    (net (code "82") (name "/VCAP_1") (class "Default")
      (node (ref "C7") (pin "1") (pinfunction "1_1") (pintype "passive"))
      (node (ref "U1") (pin "48") (pinfunction "VCAP_1_48") (pintype "passive"))
    )
    (net (code "83") (name "/VCAP_2") (class "Default")
      (node (ref "C16") (pin "1") (pinfunction "1_1") (pintype "passive"))
      (node (ref "U1") (pin "73") (pinfunction "VCAP_2_73") (pintype "passive"))
    )
    (net (code "84") (name "/VDD") (class "Default")
      (node (ref "C10") (pin "1") (pinfunction "1_1") (pintype "passive"))
      (node (ref "C11") (pin "1") (pinfunction "1_1") (pintype "passive"))
      (node (ref "C12") (pin "1") (pinfunction "1_1") (pintype "passive"))
      (node (ref "C13") (pin "1") (pinfunction "1_1") (pintype "passive"))
      (node (ref "C14") (pin "1") (pinfunction "1_1") (pintype "passive"))
      (node (ref "C15") (pin "1") (pinfunction "1_1") (pintype "passive"))
      (node (ref "C8") (pin "1") (pinfunction "1_1") (pintype "passive"))
      (node (ref "C9") (pin "1") (pinfunction "1_1") (pintype "passive"))
      (node (ref "DZ1") (pin "2") (pinfunction "K_2") (pintype "passive"))
      (node (ref "F1") (pin "2") (pinfunction "2_2") (pintype "passive"))
      (node (ref "R11") (pin "1") (pinfunction "1_1") (pintype "passive"))
      (node (ref "R29") (pin "1") (pinfunction "1_1") (pintype "passive"))
      (node (ref "R3") (pin "1") (pinfunction "1_1") (pintype "passive"))
      (node (ref "R32") (pin "1") (pinfunction "1_1") (pintype "passive"))
      (node (ref "R34") (pin "2") (pinfunction "2_2") (pintype "passive"))
      (node (ref "R6") (pin "1") (pinfunction "1_1") (pintype "passive"))
      (node (ref "R9") (pin "1") (pinfunction "1_1") (pintype "passive"))
      (node (ref "U1") (pin "100") (pinfunction "VDD_6_100") (pintype "passive"))
      (node (ref "U1") (pin "11") (pinfunction "VDD_1_11") (pintype "passive"))
      (node (ref "U1") (pin "19") (pinfunction "VDD_2_19") (pintype "passive"))
      (node (ref "U1") (pin "21") (pinfunction "VREF+_21") (pintype "passive"))
      (node (ref "U1") (pin "22") (pinfunction "VDDA_22") (pintype "passive"))
      (node (ref "U1") (pin "28") (pinfunction "VDD_3_28") (pintype "passive"))
      (node (ref "U1") (pin "50") (pinfunction "VDD_4_50") (pintype "passive"))
      (node (ref "U1") (pin "6") (pinfunction "VBAT_6") (pintype "passive"))
      (node (ref "U1") (pin "75") (pinfunction "VDD_5_75") (pintype "passive"))
    )
    (net (code "85") (name "/VSS") (class "Default")
      (node (ref "C10") (pin "2") (pinfunction "2_2") (pintype "passive"))
      (node (ref "C11") (pin "2") (pinfunction "2_2") (pintype "passive"))
      (node (ref "C12") (pin "2") (pinfunction "2_2") (pintype "passive"))
      (node (ref "C13") (pin "2") (pinfunction "2_2") (pintype "passive"))
      (node (ref "C14") (pin "2") (pinfunction "2_2") (pintype "passive"))
      (node (ref "C15") (pin "2") (pinfunction "2_2") (pintype "passive"))
      (node (ref "C16") (pin "2") (pinfunction "2_2") (pintype "passive"))
      (node (ref "C23") (pin "2") (pinfunction "2_2") (pintype "passive"))
      (node (ref "C7") (pin "2") (pinfunction "2_2") (pintype "passive"))
      (node (ref "C8") (pin "2") (pinfunction "2_2") (pintype "passive"))
      (node (ref "C9") (pin "2") (pinfunction "2_2") (pintype "passive"))
      (node (ref "D8") (pin "1") (pinfunction "CATHODE_1") (pintype "passive"))
      (node (ref "R24") (pin "2") (pinfunction "2_2") (pintype "passive"))
      (node (ref "R33") (pin "1") (pinfunction "1_1") (pintype "passive"))
      (node (ref "SW6") (pin "1") (pinfunction "1_1") (pintype "passive"))
      (node (ref "U1") (pin "10") (pinfunction "VSS_1_10") (pintype "passive"))
      (node (ref "U1") (pin "20") (pinfunction "VSSA/VREF-_20") (pintype "passive"))
      (node (ref "U1") (pin "27") (pinfunction "VSS_2_27") (pintype "passive"))
      (node (ref "U1") (pin "49") (pinfunction "VSS_3_49") (pintype "passive"))
      (node (ref "U1") (pin "74") (pinfunction "VSS_4_74") (pintype "passive"))
      (node (ref "U1") (pin "99") (pinfunction "VSS_5_99") (pintype "passive"))
    )
    (net (code "86") (name "GND") (class "Default")
      (node (ref "C20") (pin "2") (pinfunction "2_2") (pintype "passive"))
      (node (ref "J10") (pin "2") (pinfunction "2_2") (pintype "passive"))
      (node (ref "J10") (pin "6") (pinfunction "6_6") (pintype "passive"))
      (node (ref "J13") (pin "2") (pinfunction "2_2") (pintype "passive"))
      (node (ref "J13") (pin "7") (pinfunction "7_7") (pintype "passive"))
      (node (ref "J14") (pin "4") (pinfunction "4_4") (pintype "passive"))
      (node (ref "J2") (pin "3") (pinfunction "3_3") (pintype "passive"))
      (node (ref "J5") (pin "4") (pinfunction "4_4") (pintype "passive"))
      (node (ref "J6") (pin "4") (pinfunction "4_4") (pintype "passive"))
      (node (ref "J7") (pin "2") (pinfunction "2_2") (pintype "passive"))
      (node (ref "R22") (pin "2") (pinfunction "2_2") (pintype "passive"))
    )
    (net (code "87") (name "GND_EARTH") (class "Default")
      (node (ref "C24") (pin "2") (pinfunction "2_2") (pintype "passive"))
      (node (ref "C25") (pin "2") (pinfunction "2_2") (pintype "passive"))
      (node (ref "IC5") (pin "1") (pinfunction "GND_1") (pintype "power_in"))
      (node (ref "IC5") (pin "9") (pinfunction "EP_9") (pintype "passive"))
      (node (ref "R25") (pin "2") (pinfunction "2_2") (pintype "passive"))
      (node (ref "R39") (pin "2") (pinfunction "2_2") (pintype "passive"))
      (node (ref "U2") (pin "3") (pinfunction "EMITTER_3") (pintype "passive"))
      (node (ref "U3") (pin "3") (pinfunction "EMITTER_3") (pintype "passive"))
    )
    (net (code "88") (name "GND_POWER") (class "Default")
      (node (ref "C1") (pin "2") (pinfunction "2_2") (pintype "passive"))
      (node (ref "C17") (pin "2") (pinfunction "2_2") (pintype "passive"))
      (node (ref "C2") (pin "2") (pinfunction "2_2") (pintype "passive"))
      (node (ref "C3") (pin "2") (pinfunction "2_2") (pintype "passive"))
      (node (ref "C4") (pin "2") (pinfunction "2_2") (pintype "passive"))
      (node (ref "C5") (pin "2") (pinfunction "2_2") (pintype "passive"))
      (node (ref "C6") (pin "2") (pinfunction "2_2") (pintype "passive"))
      (node (ref "D5") (pin "1") (pinfunction "CATHODE_1") (pintype "passive"))
      (node (ref "D6") (pin "1") (pinfunction "CATHODE_1") (pintype "passive"))
      (node (ref "D7") (pin "1") (pinfunction "CATHODE_1") (pintype "passive"))
      (node (ref "DZ1") (pin "1") (pinfunction "A_1") (pintype "passive"))
      (node (ref "IC1") (pin "3") (pinfunction "GND_3") (pintype "power_in"))
      (node (ref "IC2") (pin "1") (pinfunction "GND_1") (pintype "passive"))
      (node (ref "IC2") (pin "2") (pinfunction "EN_2") (pintype "passive"))
      (node (ref "IC3") (pin "1") (pinfunction "ADJ/GND_1") (pintype "passive"))
      (node (ref "IC4") (pin "1") (pinfunction "ADJ/GND_1") (pintype "passive"))
      (node (ref "J1") (pin "2") (pinfunction "2_2") (pintype "passive"))
      (node (ref "J8") (pin "1") (pinfunction "1_1") (pintype "passive"))
      (node (ref "J8") (pin "3") (pinfunction "3_3") (pintype "passive"))
      (node (ref "J8") (pin "5") (pinfunction "5_5") (pintype "passive"))
      (node (ref "J9") (pin "1") (pinfunction "1_1") (pintype "passive"))
      (node (ref "J9") (pin "3") (pinfunction "3_3") (pintype "passive"))
      (node (ref "J9") (pin "5") (pinfunction "5_5") (pintype "passive"))
      (node (ref "R15") (pin "2") (pinfunction "2_2") (pintype "passive"))
      (node (ref "R22") (pin "1") (pinfunction "1_1") (pintype "passive"))
      (node (ref "R23") (pin "1") (pinfunction "1_1") (pintype "passive"))
      (node (ref "R24") (pin "1") (pinfunction "1_1") (pintype "passive"))
      (node (ref "R25") (pin "1") (pinfunction "1_1") (pintype "passive"))
      (node (ref "U2") (pin "2") (pinfunction "CATHODE_2") (pintype "passive"))
      (node (ref "U3") (pin "2") (pinfunction "CATHODE_2") (pintype "passive"))
    )
    (net (code "89") (name "GND_SIGNAL") (class "Default")
      (node (ref "C18") (pin "1") (pinfunction "1_1") (pintype "passive"))
      (node (ref "C19") (pin "1") (pinfunction "1_1") (pintype "passive"))
      (node (ref "C21") (pin "1") (pinfunction "1_1") (pintype "passive"))
      (node (ref "C22") (pin "1") (pinfunction "1_1") (pintype "passive"))
      (node (ref "J4") (pin "10") (pinfunction "10_10") (pintype "passive"))
      (node (ref "J4") (pin "12") (pinfunction "12_12") (pintype "passive"))
      (node (ref "J4") (pin "14") (pinfunction "14_14") (pintype "passive"))
      (node (ref "J4") (pin "16") (pinfunction "16_16") (pintype "passive"))
      (node (ref "J4") (pin "18") (pinfunction "18_18") (pintype "passive"))
      (node (ref "J4") (pin "20") (pinfunction "20_20") (pintype "passive"))
      (node (ref "J4") (pin "4") (pinfunction "4_4") (pintype "passive"))
      (node (ref "J4") (pin "6") (pinfunction "6_6") (pintype "passive"))
      (node (ref "J4") (pin "8") (pinfunction "8_8") (pintype "passive"))
      (node (ref "R2") (pin "2") (pinfunction "2_2") (pintype "passive"))
      (node (ref "R23") (pin "2") (pinfunction "2_2") (pintype "passive"))
      (node (ref "R28") (pin "2") (pinfunction "2_2") (pintype "passive"))
      (node (ref "R5") (pin "2") (pinfunction "2_2") (pintype "passive"))
      (node (ref "R8") (pin "2") (pinfunction "2_2") (pintype "passive"))
      (node (ref "SW2") (pin "2") (pinfunction "2_2") (pintype "passive"))
      (node (ref "SW3") (pin "2") (pinfunction "2_2") (pintype "passive"))
      (node (ref "SW4") (pin "2") (pinfunction "2_2") (pintype "passive"))
      (node (ref "SW5") (pin "2") (pinfunction "2_2") (pintype "passive"))
      (node (ref "X2") (pin "2") (pinfunction "2_2") (pintype "passive"))
      (node (ref "X2") (pin "4") (pinfunction "4_4") (pintype "passive"))
    )
    (net (code "90") (name "Net-(D1-ANODE)") (class "Default")
      (node (ref "D1") (pin "2") (pinfunction "ANODE_2") (pintype "passive"))
      (node (ref "R3") (pin "2") (pinfunction "2_2") (pintype "passive"))
    )
    (net (code "91") (name "Net-(D2-ANODE)") (class "Default")
      (node (ref "D2") (pin "2") (pinfunction "ANODE_2") (pintype "passive"))
      (node (ref "R6") (pin "2") (pinfunction "2_2") (pintype "passive"))
    )
    (net (code "92") (name "Net-(D3-ANODE)") (class "Default")
      (node (ref "D3") (pin "2") (pinfunction "ANODE_2") (pintype "passive"))
      (node (ref "R9") (pin "2") (pinfunction "2_2") (pintype "passive"))
    )
    (net (code "93") (name "Net-(D4-ANODE)") (class "Default")
      (node (ref "D4") (pin "2") (pinfunction "ANODE_2") (pintype "passive"))
      (node (ref "R11") (pin "2") (pinfunction "2_2") (pintype "passive"))
    )
    (net (code "94") (name "Net-(D5-ANODE)") (class "Default")
      (node (ref "D5") (pin "2") (pinfunction "ANODE_2") (pintype "passive"))
      (node (ref "R14") (pin "2") (pinfunction "2_2") (pintype "passive"))
    )
    (net (code "95") (name "Net-(D6-ANODE)") (class "Default")
      (node (ref "D6") (pin "2") (pinfunction "ANODE_2") (pintype "passive"))
      (node (ref "R17") (pin "2") (pinfunction "2_2") (pintype "passive"))
    )
    (net (code "96") (name "Net-(D7-ANODE)") (class "Default")
      (node (ref "D7") (pin "2") (pinfunction "ANODE_2") (pintype "passive"))
      (node (ref "R19") (pin "2") (pinfunction "2_2") (pintype "passive"))
    )
    (net (code "97") (name "Net-(D8-ANODE)") (class "Default")
      (node (ref "D8") (pin "2") (pinfunction "ANODE_2") (pintype "passive"))
      (node (ref "R29") (pin "2") (pinfunction "2_2") (pintype "passive"))
    )
    (net (code "98") (name "Net-(IC1-ADJ)") (class "Default")
      (node (ref "IC1") (pin "5") (pinfunction "ADJ_5") (pintype "power_in"))
      (node (ref "R12") (pin "2") (pinfunction "2_2") (pintype "passive"))
      (node (ref "R15") (pin "1") (pinfunction "1_1") (pintype "passive"))
    )
    (net (code "99") (name "Net-(IC1-VOUT)") (class "Default")
      (node (ref "C3") (pin "1") (pinfunction "1_1") (pintype "passive"))
      (node (ref "IC1") (pin "4") (pinfunction "VOUT_4") (pintype "power_in"))
      (node (ref "R12") (pin "1") (pinfunction "1_1") (pintype "passive"))
      (node (ref "RF1") (pin "1") (pinfunction "1_1") (pintype "passive"))
    )
    (net (code "100") (name "Net-(IC5-ISEN)") (class "Default")
      (node (ref "IC5") (pin "7") (pinfunction "ISEN_7") (pintype "power_in"))
      (node (ref "R39") (pin "1") (pinfunction "1_1") (pintype "passive"))
    )
    (net (code "101") (name "Net-(J1-Pad1)") (class "Default")
      (node (ref "J1") (pin "1") (pinfunction "1_1") (pintype "passive"))
      (node (ref "S1") (pin "2") (pinfunction "2_2") (pintype "passive"))
    )
    (net (code "102") (name "Net-(R2-Pad1)") (class "Default")
      (node (ref "R2") (pin "1") (pinfunction "1_1") (pintype "passive"))
      (node (ref "SW1") (pin "6") (pinfunction "6_6") (pintype "passive"))
    )
    (net (code "103") (name "Net-(R5-Pad1)") (class "Default")
      (node (ref "R5") (pin "1") (pinfunction "1_1") (pintype "passive"))
      (node (ref "SW1") (pin "5") (pinfunction "5_5") (pintype "passive"))
    )
    (net (code "104") (name "Net-(R8-Pad1)") (class "Default")
      (node (ref "R8") (pin "1") (pinfunction "1_1") (pintype "passive"))
      (node (ref "SW1") (pin "4") (pinfunction "4_4") (pintype "passive"))
    )
    (net (code "105") (name "Net-(U2-ANODE)") (class "Default")
      (node (ref "R36") (pin "2") (pinfunction "2_2") (pintype "passive"))
      (node (ref "U2") (pin "1") (pinfunction "ANODE_1") (pintype "passive"))
    )
    (net (code "106") (name "Net-(U3-ANODE)") (class "Default")
      (node (ref "R38") (pin "2") (pinfunction "2_2") (pintype "passive"))
      (node (ref "U3") (pin "1") (pinfunction "ANODE_1") (pintype "passive"))
    )
    (net (code "107") (name "unconnected-(IC2-FB{slash}NC-Pad7)") (class "Default")
      (node (ref "IC2") (pin "7") (pinfunction "FB/NC_7") (pintype "passive"))
    )
    (net (code "108") (name "unconnected-(IC2-PG-Pad8)") (class "Default")
      (node (ref "IC2") (pin "8") (pinfunction "PG_8") (pintype "passive"))
    )
    (net (code "109") (name "unconnected-(IC3-GND-Pad4)") (class "Default")
      (node (ref "IC3") (pin "4") (pinfunction "GND_4") (pintype "power_in"))
    )
    (net (code "110") (name "unconnected-(IC4-GND-Pad4)") (class "Default")
      (node (ref "IC4") (pin "4") (pinfunction "GND_4") (pintype "power_in"))
    )
    (net (code "111") (name "unconnected-(J4-Pad11)") (class "Default")
      (node (ref "J4") (pin "11") (pinfunction "11_11") (pintype "passive"))
    )
    (net (code "112") (name "unconnected-(J4-Pad17)") (class "Default")
      (node (ref "J4") (pin "17") (pinfunction "17_17") (pintype "passive"))
    )
    (net (code "113") (name "unconnected-(J4-Pad19)") (class "Default")
      (node (ref "J4") (pin "19") (pinfunction "19_19") (pintype "passive"))
    )
    (net (code "114") (name "unconnected-(J5-Pad1)") (class "Default")
      (node (ref "J5") (pin "1") (pinfunction "1_1") (pintype "passive"))
    )
    (net (code "115") (name "unconnected-(J5-Pad6)") (class "Default")
      (node (ref "J5") (pin "6") (pinfunction "6_6") (pintype "passive"))
    )
    (net (code "116") (name "unconnected-(J6-Pad3)") (class "Default")
      (node (ref "J6") (pin "3") (pinfunction "3_3") (pintype "passive"))
    )
    (net (code "117") (name "unconnected-(J6-Pad8)") (class "Default")
      (node (ref "J6") (pin "8") (pinfunction "8_8") (pintype "passive"))
    )
    (net (code "118") (name "unconnected-(J6-Pad9)") (class "Default")
      (node (ref "J6") (pin "9") (pinfunction "9_9") (pintype "passive"))
    )
    (net (code "119") (name "unconnected-(J10-Pad7)") (class "Default")
      (node (ref "J10") (pin "7") (pinfunction "7_7") (pintype "passive"))
    )
    (net (code "120") (name "unconnected-(J10-Pad8)") (class "Default")
      (node (ref "J10") (pin "8") (pinfunction "8_8") (pintype "passive"))
    )
    (net (code "121") (name "unconnected-(J12-Pad10)") (class "Default")
      (node (ref "J12") (pin "10") (pinfunction "10_10") (pintype "passive"))
    )
    (net (code "122") (name "unconnected-(S1-Pad1)") (class "Default")
      (node (ref "S1") (pin "1") (pinfunction "1_1") (pintype "passive"))
    )
    (net (code "123") (name "unconnected-(U1-PA2-Pad25)") (class "Default")
      (node (ref "U1") (pin "25") (pinfunction "PA2_25") (pintype "passive"))
    )
    (net (code "124") (name "unconnected-(U1-PA3-Pad26)") (class "Default")
      (node (ref "U1") (pin "26") (pinfunction "PA3_26") (pintype "passive"))
    )
    (net (code "125") (name "unconnected-(U1-PA8-Pad67)") (class "Default")
      (node (ref "U1") (pin "67") (pinfunction "PA8_67") (pintype "passive"))
    )
    (net (code "126") (name "unconnected-(U1-PA11-Pad70)") (class "Default")
      (node (ref "U1") (pin "70") (pinfunction "PA11_70") (pintype "passive"))
    )
    (net (code "127") (name "unconnected-(U1-PA12-Pad71)") (class "Default")
      (node (ref "U1") (pin "71") (pinfunction "PA12_71") (pintype "passive"))
    )
    (net (code "128") (name "unconnected-(U1-PC0-Pad15)") (class "Default")
      (node (ref "U1") (pin "15") (pinfunction "PC0_15") (pintype "passive"))
    )
    (net (code "129") (name "unconnected-(U1-PC3-Pad18)") (class "Default")
      (node (ref "U1") (pin "18") (pinfunction "PC3_18") (pintype "passive"))
    )
    (net (code "130") (name "unconnected-(U1-PC9-Pad66)") (class "Default")
      (node (ref "U1") (pin "66") (pinfunction "PC9_66") (pintype "passive"))
    )
    (net (code "131") (name "unconnected-(U1-PE0-Pad97)") (class "Default")
      (node (ref "U1") (pin "97") (pinfunction "PE0_97") (pintype "passive"))
    )
    (net (code "132") (name "unconnected-(U1-PE3-Pad2)") (class "Default")
      (node (ref "U1") (pin "2") (pinfunction "PE3_2") (pintype "passive"))
    )
    (net (code "133") (name "unconnected-(U1-PE13-Pad44)") (class "Default")
      (node (ref "U1") (pin "44") (pinfunction "PE13_44") (pintype "passive"))
    )
    (net (code "134") (name "unconnected-(X1-Pad2)") (class "Default")
      (node (ref "X1") (pin "2") (pinfunction "2_2") (pintype "passive"))
    )
    (net (code "135") (name "unconnected-(X1-Pad3)") (class "Default")
      (node (ref "X1") (pin "3") (pinfunction "3_3") (pintype "passive"))
    )
  )
)
